# Digital_Voltimeter.net
KiCad netlist of a schematic drawn in Altium Designer
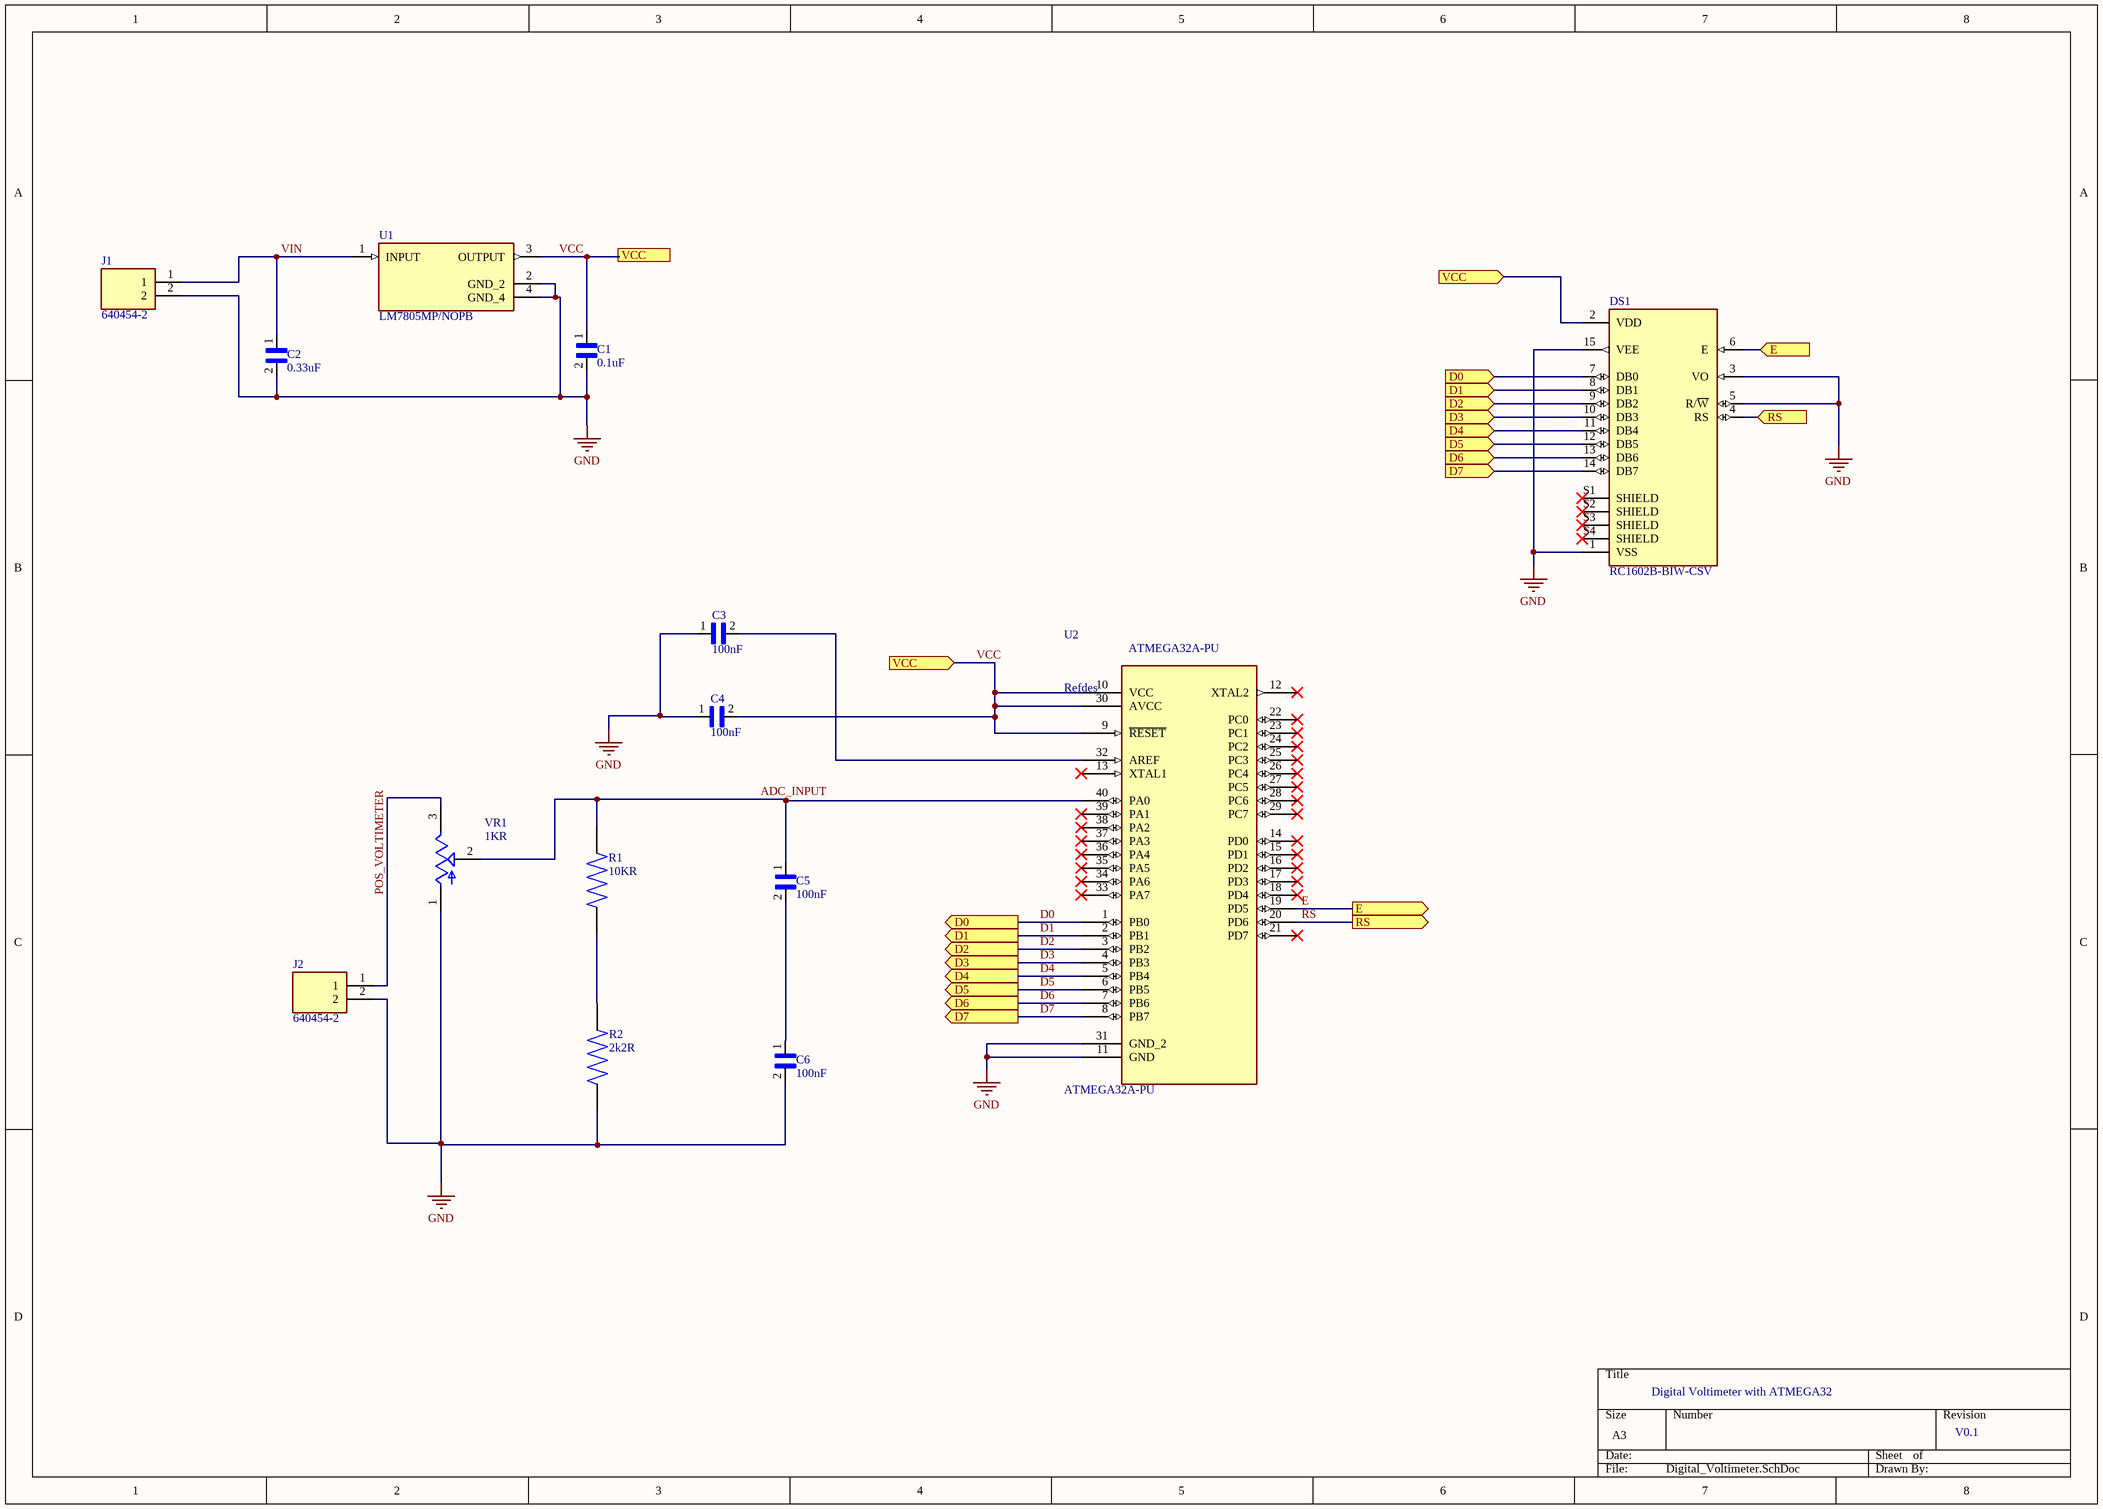
[diagram p0: Digital_Voltimeter.SchDoc]

(export (version "E")
  (design (tool "Eeschema 10.0.6"))
  (components
    (comp (ref "C1")
      (value "0.1uF")
      (footprint "CAPRR1500W60L1820T520H1540")
      (fields (field (name "MP") "ECWFA2J104JQ"))
      (libsource (lib "Capacitor_0_1uF") (part "ECWFA2J104JQ"))
    )
    (comp (ref "C2")
      (value "0.33uF")
      (footprint "CAPRB250W50L550T350H600")
      (description "0.33 ÂµF Â±10% 100V Ceramic Capacitor X8R Radial")
      (fields (field (name "MP") "FA16X8R2A334KRU00") (field (name "MF") "TDK"))
      (libsource (lib "Capacitor_0_33uF") (part "FA16X8R2A334KRU00"))
    )
    (comp (ref "C3")
      (value "100nF")
      (footprint "CAPC1608X90N")
      (description "CERAMIC CAPACITOR, 0.1UF, 16V, X7R, 10%, 0603, FULL REEL")
      (fields (field (name "MP") "0603YC104KAZ2A"))
      (libsource (lib "") (part "0603YC104KAZ2A_1"))
    )
    (comp (ref "C4")
      (value "100nF")
      (footprint "CAPC1608X90N")
      (description "CERAMIC CAPACITOR, 0.1UF, 16V, X7R, 10%, 0603, FULL REEL")
      (fields (field (name "MP") "0603YC104KAZ2A"))
      (libsource (lib "") (part "0603YC104KAZ2A_1"))
    )
    (comp (ref "C5")
      (value "100nF")
      (footprint "CAPC1608X90N")
      (description "CERAMIC CAPACITOR, 0.1UF, 16V, X7R, 10%, 0603, FULL REEL")
      (fields (field (name "MP") "0603YC104KAZ2A"))
      (libsource (lib "0603YC104KAZ2A") (part "0603YC104KAZ2A"))
    )
    (comp (ref "C6")
      (value "100nF")
      (footprint "CAPC1608X90N")
      (description "CERAMIC CAPACITOR, 0.1UF, 16V, X7R, 10%, 0603, FULL REEL")
      (fields (field (name "MP") "0603YC104KAZ2A"))
      (libsource (lib "0603YC104KAZ2A") (part "0603YC104KAZ2A"))
    )
    (comp (ref "DS1")
      (value "RC1602B-BIW-CSV")
      (footprint "LCD_RC1602B-BIW-CSV")
      (description "Display: LCD; alphanumeric; STN Negative; 16x2; blue; LED; PIN: 16")
      (fields (field (name "MF") "Raystar"))
      (libsource (lib "RC1602B-BIW-CSV") (part "RC1602B-BIW-CSV"))
    )
    (comp (ref "J1")
      (value "640454-2")
      (footprint "TE_640454-2")
      (description "02P MTA100 HDR ASSY SQ STR POL")
      (fields (field (name "MF") "TE Connectivity"))
      (libsource (lib "Input_Connector_2pin") (part "640454-2"))
    )
    (comp (ref "J2")
      (value "640454-2")
      (footprint "TE_640454-2")
      (description "02P MTA100 HDR ASSY SQ STR POL")
      (fields (field (name "MF") "TE Connectivity"))
      (libsource (lib "Input_Connector_2pin") (part "640454-2"))
    )
    (comp (ref "R1")
      (value "10KR")
      (footprint "RESC3115X65N")
      (description "Fixed Resistor CRGCQ 1206 10K 5%")
      (fields (field (name "MF") "TE Connectivity") (field (name "MP") "CRGCQ1206J10K"))
      (libsource (lib "RES10K_1206") (part "CRGCQ1206J10K"))
    )
    (comp (ref "R2")
      (value "2k2R")
      (footprint "RESC3126X65N")
      (description "Fixed Resistor CRGCQ 1210 2K2 5%")
      (fields (field (name "MP") "CRGCQ1210J2K2"))
      (libsource (lib "Res2K2_1210") (part "CRGCQ1210J2K2"))
    )
    (comp (ref "U1")
      (value "LM7805MP/NOPB")
      (footprint "VREG_LM7805MP/NOPB")
      (description "1.5-A, 30-V, linear voltage regulator")
      (fields (field (name "MF") "Texas Instruments"))
      (libsource (lib "LM7805MP_NOPB") (part "LM7805MP/NOPB"))
    )
    (comp (ref "U2")
      (value "ATMEGA32A-PU")
      (footprint "DIP254P1524X482-40")
      (description "AVR AVRÂ® ATmega Microcontroller IC 8-Bit 16MHz 32KB (16K x 16) FLASH 40-PDIP")
      (fields (field (name "MF") "Microchip"))
      (libsource (lib "ATMEGA32A-PU") (part "ATMEGA32A-PU"))
    )
    (comp (ref "VR1")
      (value "1KR")
      (footprint "TRIM_3362P-1-253LF")
      (description "25 kOhms 0.5W, 1/2W PC Pins Through Hole Trimmer Potentiometer Cermet 1.0 Turn Top Adjustment")
      (fields (field (name "MF") "Bourns") (field (name "MP") "3362P-1-253LF"))
      (libsource (lib "Trimpot_1KR") (part "3362P-1-253LF"))
    )
  )
  (nets
    (net (code "1") (name "/ADC_INPUT") (class "Default")
      (node (ref "C5") (pin "1") (pinfunction "1_1") (pintype "passive"))
      (node (ref "R1") (pin "2") (pinfunction "2_2") (pintype "passive"))
      (node (ref "U2") (pin "40") (pinfunction "PA0_40") (pintype "bidirectional"))
      (node (ref "VR1") (pin "2") (pinfunction "WIPER_2") (pintype "passive"))
    )
    (net (code "2") (name "/D0") (class "Default")
      (node (ref "DS1") (pin "7") (pinfunction "DB0_7") (pintype "bidirectional"))
      (node (ref "U2") (pin "1") (pinfunction "PB0_1") (pintype "bidirectional"))
    )
    (net (code "3") (name "/D1") (class "Default")
      (node (ref "DS1") (pin "8") (pinfunction "DB1_8") (pintype "bidirectional"))
      (node (ref "U2") (pin "2") (pinfunction "PB1_2") (pintype "bidirectional"))
    )
    (net (code "4") (name "/D2") (class "Default")
      (node (ref "DS1") (pin "9") (pinfunction "DB2_9") (pintype "bidirectional"))
      (node (ref "U2") (pin "3") (pinfunction "PB2_3") (pintype "bidirectional"))
    )
    (net (code "5") (name "/D3") (class "Default")
      (node (ref "DS1") (pin "10") (pinfunction "DB3_10") (pintype "bidirectional"))
      (node (ref "U2") (pin "4") (pinfunction "PB3_4") (pintype "bidirectional"))
    )
    (net (code "6") (name "/D4") (class "Default")
      (node (ref "DS1") (pin "11") (pinfunction "DB4_11") (pintype "bidirectional"))
      (node (ref "U2") (pin "5") (pinfunction "PB4_5") (pintype "bidirectional"))
    )
    (net (code "7") (name "/D5") (class "Default")
      (node (ref "DS1") (pin "12") (pinfunction "DB5_12") (pintype "bidirectional"))
      (node (ref "U2") (pin "6") (pinfunction "PB5_6") (pintype "bidirectional"))
    )
    (net (code "8") (name "/D6") (class "Default")
      (node (ref "DS1") (pin "13") (pinfunction "DB6_13") (pintype "bidirectional"))
      (node (ref "U2") (pin "7") (pinfunction "PB6_7") (pintype "bidirectional"))
    )
    (net (code "9") (name "/D7") (class "Default")
      (node (ref "DS1") (pin "14") (pinfunction "DB7_14") (pintype "bidirectional"))
      (node (ref "U2") (pin "8") (pinfunction "PB7_8") (pintype "bidirectional"))
    )
    (net (code "10") (name "/E") (class "Default")
      (node (ref "DS1") (pin "6") (pinfunction "E_6") (pintype "input"))
      (node (ref "U2") (pin "19") (pinfunction "PD5_19") (pintype "bidirectional"))
    )
    (net (code "11") (name "/POS_VOLTIMETER") (class "Default")
      (node (ref "J2") (pin "1") (pinfunction "1_1") (pintype "passive"))
      (node (ref "VR1") (pin "3") (pinfunction "CW_3") (pintype "passive"))
    )
    (net (code "12") (name "/RS") (class "Default")
      (node (ref "DS1") (pin "4") (pinfunction "RS_4") (pintype "bidirectional"))
      (node (ref "U2") (pin "20") (pinfunction "PD6_20") (pintype "bidirectional"))
    )
    (net (code "13") (name "/VCC") (class "Default")
      (node (ref "C1") (pin "1") (pinfunction "1_1") (pintype "passive"))
      (node (ref "C4") (pin "2") (pinfunction "2_2") (pintype "passive"))
      (node (ref "DS1") (pin "2") (pinfunction "VDD_2") (pintype "power_in"))
      (node (ref "U1") (pin "3") (pinfunction "OUTPUT_3") (pintype "output"))
      (node (ref "U2") (pin "10") (pinfunction "VCC_10") (pintype "power_in"))
      (node (ref "U2") (pin "30") (pinfunction "AVCC_30") (pintype "power_in"))
      (node (ref "U2") (pin "9") (pinfunction "~{RESET}_9") (pintype "input"))
    )
    (net (code "14") (name "/VIN") (class "Default")
      (node (ref "C2") (pin "1") (pinfunction "1_1") (pintype "passive"))
      (node (ref "J1") (pin "1") (pinfunction "1_1") (pintype "passive"))
      (node (ref "U1") (pin "1") (pinfunction "INPUT_1") (pintype "input"))
    )
    (net (code "15") (name "GND") (class "Default")
      (node (ref "C1") (pin "2") (pinfunction "2_2") (pintype "passive"))
      (node (ref "C2") (pin "2") (pinfunction "2_2") (pintype "passive"))
      (node (ref "C3") (pin "1") (pinfunction "1_1") (pintype "passive"))
      (node (ref "C4") (pin "1") (pinfunction "1_1") (pintype "passive"))
      (node (ref "C6") (pin "2") (pinfunction "2_2") (pintype "passive"))
      (node (ref "DS1") (pin "1") (pinfunction "VSS_1") (pintype "power_in"))
      (node (ref "DS1") (pin "15") (pinfunction "VEE_15") (pintype "output"))
      (node (ref "DS1") (pin "3") (pinfunction "VO_3") (pintype "input"))
      (node (ref "DS1") (pin "5") (pinfunction "R/~{W}_5") (pintype "bidirectional"))
      (node (ref "J1") (pin "2") (pinfunction "2_2") (pintype "passive"))
      (node (ref "J2") (pin "2") (pinfunction "2_2") (pintype "passive"))
      (node (ref "R2") (pin "1") (pinfunction "1_1") (pintype "passive"))
      (node (ref "U1") (pin "2") (pinfunction "GND_2_2") (pintype "power_in"))
      (node (ref "U1") (pin "4") (pinfunction "GND_4_4") (pintype "power_in"))
      (node (ref "U2") (pin "11") (pinfunction "GND_11") (pintype "passive"))
      (node (ref "U2") (pin "31") (pinfunction "GND_2_31") (pintype "passive"))
      (node (ref "VR1") (pin "1") (pinfunction "CCW_1") (pintype "passive"))
    )
    (net (code "16") (name "Net-(C5-Pad2)") (class "Default")
      (node (ref "C5") (pin "2") (pinfunction "2_2") (pintype "passive"))
      (node (ref "C6") (pin "1") (pinfunction "1_1") (pintype "passive"))
    )
    (net (code "17") (name "Net-(R1-Pad1)") (class "Default")
      (node (ref "R1") (pin "1") (pinfunction "1_1") (pintype "passive"))
      (node (ref "R2") (pin "2") (pinfunction "2_2") (pintype "passive"))
    )
    (net (code "18") (name "Net-(U2-AREF)") (class "Default")
      (node (ref "C3") (pin "2") (pinfunction "2_2") (pintype "passive"))
      (node (ref "U2") (pin "32") (pinfunction "AREF_32") (pintype "input"))
    )
    (net (code "19") (name "unconnected-(DS1-SHIELD-PadS1)") (class "Default")
      (node (ref "DS1") (pin "S1") (pinfunction "SHIELD_S1") (pintype "passive+no_connect"))
    )
    (net (code "20") (name "unconnected-(DS1-SHIELD-PadS2)") (class "Default")
      (node (ref "DS1") (pin "S2") (pinfunction "SHIELD_S2") (pintype "passive+no_connect"))
    )
    (net (code "21") (name "unconnected-(DS1-SHIELD-PadS3)") (class "Default")
      (node (ref "DS1") (pin "S3") (pinfunction "SHIELD_S3") (pintype "passive+no_connect"))
    )
    (net (code "22") (name "unconnected-(DS1-SHIELD-PadS4)") (class "Default")
      (node (ref "DS1") (pin "S4") (pinfunction "SHIELD_S4") (pintype "passive+no_connect"))
    )
    (net (code "23") (name "unconnected-(U2-PA1-Pad39)") (class "Default")
      (node (ref "U2") (pin "39") (pinfunction "PA1_39") (pintype "bidirectional+no_connect"))
    )
    (net (code "24") (name "unconnected-(U2-PA2-Pad38)") (class "Default")
      (node (ref "U2") (pin "38") (pinfunction "PA2_38") (pintype "bidirectional+no_connect"))
    )
    (net (code "25") (name "unconnected-(U2-PA3-Pad37)") (class "Default")
      (node (ref "U2") (pin "37") (pinfunction "PA3_37") (pintype "bidirectional+no_connect"))
    )
    (net (code "26") (name "unconnected-(U2-PA4-Pad36)") (class "Default")
      (node (ref "U2") (pin "36") (pinfunction "PA4_36") (pintype "bidirectional+no_connect"))
    )
    (net (code "27") (name "unconnected-(U2-PA5-Pad35)") (class "Default")
      (node (ref "U2") (pin "35") (pinfunction "PA5_35") (pintype "bidirectional+no_connect"))
    )
    (net (code "28") (name "unconnected-(U2-PA6-Pad34)") (class "Default")
      (node (ref "U2") (pin "34") (pinfunction "PA6_34") (pintype "bidirectional+no_connect"))
    )
    (net (code "29") (name "unconnected-(U2-PA7-Pad33)") (class "Default")
      (node (ref "U2") (pin "33") (pinfunction "PA7_33") (pintype "bidirectional+no_connect"))
    )
    (net (code "30") (name "unconnected-(U2-PC0-Pad22)") (class "Default")
      (node (ref "U2") (pin "22") (pinfunction "PC0_22") (pintype "bidirectional+no_connect"))
    )
    (net (code "31") (name "unconnected-(U2-PC1-Pad23)") (class "Default")
      (node (ref "U2") (pin "23") (pinfunction "PC1_23") (pintype "bidirectional+no_connect"))
    )
    (net (code "32") (name "unconnected-(U2-PC2-Pad24)") (class "Default")
      (node (ref "U2") (pin "24") (pinfunction "PC2_24") (pintype "bidirectional+no_connect"))
    )
    (net (code "33") (name "unconnected-(U2-PC3-Pad25)") (class "Default")
      (node (ref "U2") (pin "25") (pinfunction "PC3_25") (pintype "bidirectional+no_connect"))
    )
    (net (code "34") (name "unconnected-(U2-PC4-Pad26)") (class "Default")
      (node (ref "U2") (pin "26") (pinfunction "PC4_26") (pintype "bidirectional+no_connect"))
    )
    (net (code "35") (name "unconnected-(U2-PC5-Pad27)") (class "Default")
      (node (ref "U2") (pin "27") (pinfunction "PC5_27") (pintype "bidirectional+no_connect"))
    )
    (net (code "36") (name "unconnected-(U2-PC6-Pad28)") (class "Default")
      (node (ref "U2") (pin "28") (pinfunction "PC6_28") (pintype "bidirectional+no_connect"))
    )
    (net (code "37") (name "unconnected-(U2-PC7-Pad29)") (class "Default")
      (node (ref "U2") (pin "29") (pinfunction "PC7_29") (pintype "bidirectional+no_connect"))
    )
    (net (code "38") (name "unconnected-(U2-PD0-Pad14)") (class "Default")
      (node (ref "U2") (pin "14") (pinfunction "PD0_14") (pintype "bidirectional+no_connect"))
    )
    (net (code "39") (name "unconnected-(U2-PD1-Pad15)") (class "Default")
      (node (ref "U2") (pin "15") (pinfunction "PD1_15") (pintype "bidirectional+no_connect"))
    )
    (net (code "40") (name "unconnected-(U2-PD2-Pad16)") (class "Default")
      (node (ref "U2") (pin "16") (pinfunction "PD2_16") (pintype "bidirectional+no_connect"))
    )
    (net (code "41") (name "unconnected-(U2-PD3-Pad17)") (class "Default")
      (node (ref "U2") (pin "17") (pinfunction "PD3_17") (pintype "bidirectional+no_connect"))
    )
    (net (code "42") (name "unconnected-(U2-PD4-Pad18)") (class "Default")
      (node (ref "U2") (pin "18") (pinfunction "PD4_18") (pintype "bidirectional+no_connect"))
    )
    (net (code "43") (name "unconnected-(U2-PD7-Pad21)") (class "Default")
      (node (ref "U2") (pin "21") (pinfunction "PD7_21") (pintype "bidirectional+no_connect"))
    )
    (net (code "44") (name "unconnected-(U2-XTAL1-Pad13)") (class "Default")
      (node (ref "U2") (pin "13") (pinfunction "XTAL1_13") (pintype "input+no_connect"))
    )
    (net (code "45") (name "unconnected-(U2-XTAL2-Pad12)") (class "Default")
      (node (ref "U2") (pin "12") (pinfunction "XTAL2_12") (pintype "output+no_connect"))
    )
  )
)
